# PGTN021_octasource_mkiii_panel.net
KiCad netlist of a schematic drawn in EAGLE
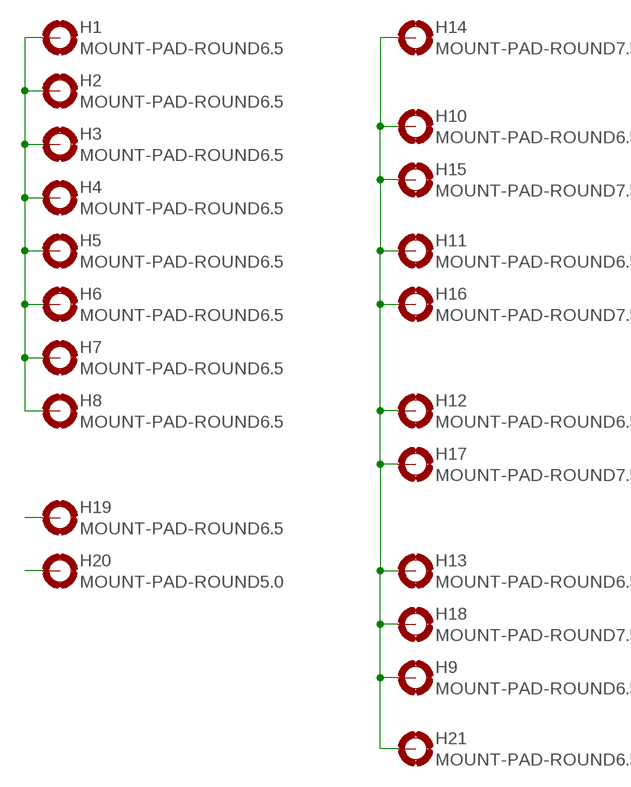
[diagram p0: schematic, sheet 1]

(export (version "E")
  (design (tool "Eeschema 10.0.6"))
  (components
    (comp (ref "H1")
      (value "MOUNT-PAD-ROUND6.5")
      (footprint "eagle-import:6.5-PAD")
      (libsource (lib "eagle-import") (part "MOUNT-PAD-ROUND6.5"))
    )
    (comp (ref "H2")
      (value "MOUNT-PAD-ROUND6.5")
      (footprint "eagle-import:6.5-PAD")
      (libsource (lib "eagle-import") (part "MOUNT-PAD-ROUND6.5"))
    )
    (comp (ref "H3")
      (value "MOUNT-PAD-ROUND6.5")
      (footprint "eagle-import:6.5-PAD")
      (libsource (lib "eagle-import") (part "MOUNT-PAD-ROUND6.5"))
    )
    (comp (ref "H4")
      (value "MOUNT-PAD-ROUND6.5")
      (footprint "eagle-import:6.5-PAD")
      (libsource (lib "eagle-import") (part "MOUNT-PAD-ROUND6.5"))
    )
    (comp (ref "H5")
      (value "MOUNT-PAD-ROUND6.5")
      (footprint "eagle-import:6.5-PAD")
      (libsource (lib "eagle-import") (part "MOUNT-PAD-ROUND6.5"))
    )
    (comp (ref "H6")
      (value "MOUNT-PAD-ROUND6.5")
      (footprint "eagle-import:6.5-PAD")
      (libsource (lib "eagle-import") (part "MOUNT-PAD-ROUND6.5"))
    )
    (comp (ref "H7")
      (value "MOUNT-PAD-ROUND6.5")
      (footprint "eagle-import:6.5-PAD")
      (libsource (lib "eagle-import") (part "MOUNT-PAD-ROUND6.5"))
    )
    (comp (ref "H8")
      (value "MOUNT-PAD-ROUND6.5")
      (footprint "eagle-import:6.5-PAD")
      (libsource (lib "eagle-import") (part "MOUNT-PAD-ROUND6.5"))
    )
    (comp (ref "H9")
      (value "MOUNT-PAD-ROUND6.5")
      (footprint "eagle-import:6.5-PAD")
      (libsource (lib "eagle-import") (part "MOUNT-PAD-ROUND6.5"))
    )
    (comp (ref "H10")
      (value "MOUNT-PAD-ROUND6.5")
      (footprint "eagle-import:6.5-PAD")
      (libsource (lib "eagle-import") (part "MOUNT-PAD-ROUND6.5"))
    )
    (comp (ref "H11")
      (value "MOUNT-PAD-ROUND6.5")
      (footprint "eagle-import:6.5-PAD")
      (libsource (lib "eagle-import") (part "MOUNT-PAD-ROUND6.5"))
    )
    (comp (ref "H12")
      (value "MOUNT-PAD-ROUND6.5")
      (footprint "eagle-import:6.5-PAD")
      (libsource (lib "eagle-import") (part "MOUNT-PAD-ROUND6.5"))
    )
    (comp (ref "H13")
      (value "MOUNT-PAD-ROUND6.5")
      (footprint "eagle-import:6.5-PAD")
      (libsource (lib "eagle-import") (part "MOUNT-PAD-ROUND6.5"))
    )
    (comp (ref "H14")
      (value "MOUNT-PAD-ROUND7.5")
      (footprint "eagle-import:7.5-PAD")
      (libsource (lib "eagle-import") (part "MOUNT-PAD-ROUND7.5"))
    )
    (comp (ref "H15")
      (value "MOUNT-PAD-ROUND7.5")
      (footprint "eagle-import:7.5-PAD")
      (libsource (lib "eagle-import") (part "MOUNT-PAD-ROUND7.5"))
    )
    (comp (ref "H16")
      (value "MOUNT-PAD-ROUND7.5")
      (footprint "eagle-import:7.5-PAD")
      (libsource (lib "eagle-import") (part "MOUNT-PAD-ROUND7.5"))
    )
    (comp (ref "H17")
      (value "MOUNT-PAD-ROUND7.5")
      (footprint "eagle-import:7.5-PAD")
      (libsource (lib "eagle-import") (part "MOUNT-PAD-ROUND7.5"))
    )
    (comp (ref "H18")
      (value "MOUNT-PAD-ROUND7.5")
      (footprint "eagle-import:7.5-PAD")
      (libsource (lib "eagle-import") (part "MOUNT-PAD-ROUND7.5"))
    )
    (comp (ref "H19")
      (value "MOUNT-PAD-ROUND6.5")
      (footprint "eagle-import:6.5-PAD")
      (libsource (lib "eagle-import") (part "MOUNT-PAD-ROUND6.5"))
    )
    (comp (ref "H20")
      (value "MOUNT-PAD-ROUND5.0")
      (footprint "eagle-import:5,0-PAD")
      (libsource (lib "eagle-import") (part "MOUNT-PAD-ROUND5.0"))
    )
    (comp (ref "H21")
      (value "MOUNT-PAD-ROUND6.5")
      (footprint "eagle-import:6.5-PAD")
      (libsource (lib "eagle-import") (part "MOUNT-PAD-ROUND6.5"))
    )
  )
  (nets
    (net (code "1") (name "Net-(H1-MOUNT)") (class "Default")
      (node (ref "H1") (pin "B6.5") (pinfunction "MOUNT_B6.5") (pintype "passive"))
      (node (ref "H2") (pin "B6.5") (pinfunction "MOUNT_B6.5") (pintype "passive"))
      (node (ref "H3") (pin "B6.5") (pinfunction "MOUNT_B6.5") (pintype "passive"))
      (node (ref "H4") (pin "B6.5") (pinfunction "MOUNT_B6.5") (pintype "passive"))
      (node (ref "H5") (pin "B6.5") (pinfunction "MOUNT_B6.5") (pintype "passive"))
      (node (ref "H6") (pin "B6.5") (pinfunction "MOUNT_B6.5") (pintype "passive"))
      (node (ref "H7") (pin "B6.5") (pinfunction "MOUNT_B6.5") (pintype "passive"))
      (node (ref "H8") (pin "B6.5") (pinfunction "MOUNT_B6.5") (pintype "passive"))
    )
    (net (code "2") (name "Net-(H10-MOUNT)") (class "Default")
      (node (ref "H10") (pin "B6.5") (pinfunction "MOUNT_B6.5") (pintype "passive"))
      (node (ref "H11") (pin "B6.5") (pinfunction "MOUNT_B6.5") (pintype "passive"))
      (node (ref "H12") (pin "B6.5") (pinfunction "MOUNT_B6.5") (pintype "passive"))
      (node (ref "H13") (pin "B6.5") (pinfunction "MOUNT_B6.5") (pintype "passive"))
      (node (ref "H14") (pin "B7.5") (pinfunction "MOUNT_B7.5") (pintype "passive"))
      (node (ref "H15") (pin "B7.5") (pinfunction "MOUNT_B7.5") (pintype "passive"))
      (node (ref "H16") (pin "B7.5") (pinfunction "MOUNT_B7.5") (pintype "passive"))
      (node (ref "H17") (pin "B7.5") (pinfunction "MOUNT_B7.5") (pintype "passive"))
      (node (ref "H18") (pin "B7.5") (pinfunction "MOUNT_B7.5") (pintype "passive"))
      (node (ref "H21") (pin "B6.5") (pinfunction "MOUNT_B6.5") (pintype "passive"))
      (node (ref "H9") (pin "B6.5") (pinfunction "MOUNT_B6.5") (pintype "passive"))
    )
    (net (code "3") (name "unconnected-(H19-MOUNT-PadB6.5)") (class "Default")
      (node (ref "H19") (pin "B6.5") (pinfunction "MOUNT_B6.5") (pintype "passive"))
    )
    (net (code "4") (name "unconnected-(H20-MOUNT-PadB5)") (class "Default")
      (node (ref "H20") (pin "B5") (pinfunction "MOUNT_B5") (pintype "passive"))
    )
  )
)
